# Sheet7.net
KiCad netlist of a schematic drawn in Altium Designer
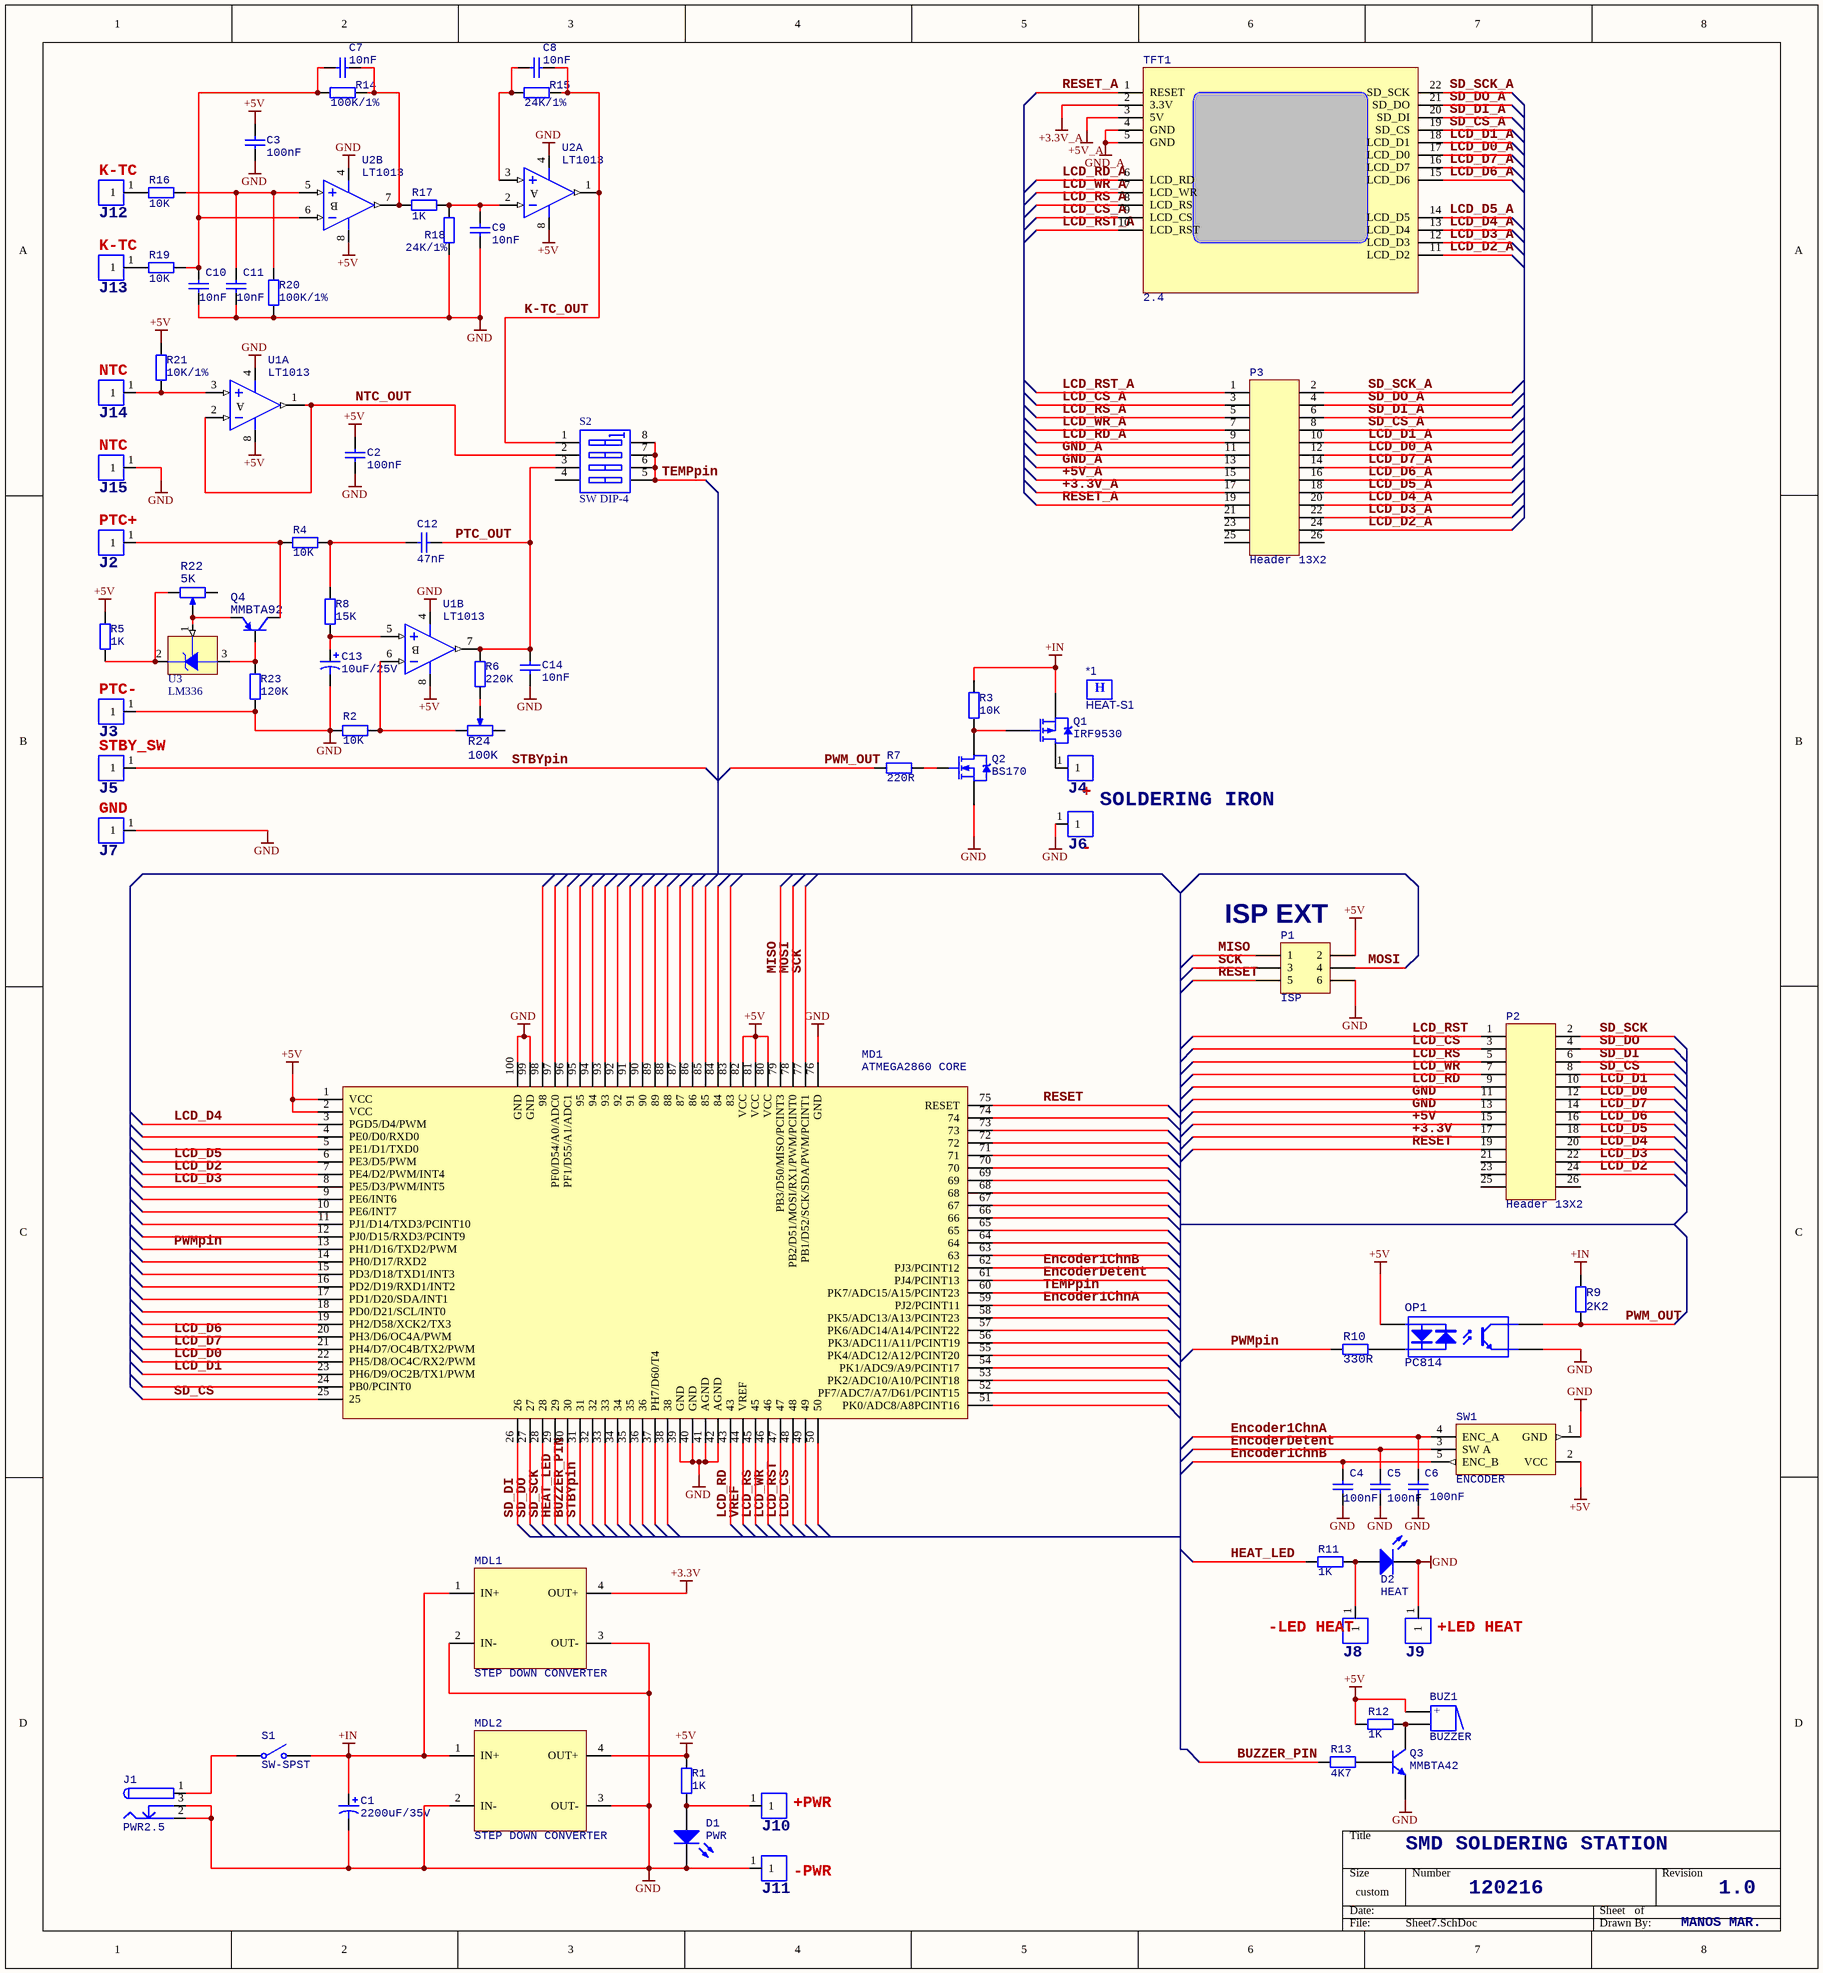
[diagram p0: Sheet7.SchDoc]

(export (version "E")
  (design (tool "Eeschema 10.0.6"))
  (components
    (comp (ref "*1")
      (value "HEAT-S1")
      (footprint "SK 104 HEATSHINK")
      (libsource (lib "SG_INTLIB") (part "HEAT-S1"))
    )
    (comp (ref "BUZ1") (value "BUZZER") (footprint "BUZZER") (libsource (lib "SMD STATION") (part "BUZZER")))
    (comp (ref "C1")
      (value "2200uF/35V")
      (footprint "RB5-10.5")
      (description "Polarized Capacitor (Radial)")
      (libsource (lib "Miscellaneous Devices") (part "Cap Pol1"))
    )
    (comp (ref "C2")
      (value "100nF")
      (footprint "0805")
      (description "Capacitor, Ceramic, 4.7uF 10% 16V 0805 (2012) X7R")
      (fields (field (name "TOLERANCE") "10 %"))
      (libsource (lib "AltiumDesignLibrary") (part "CAP-NP"))
    )
    (comp (ref "C3")
      (value "100nF")
      (footprint "0805")
      (description "Capacitor, Ceramic, 4.7uF 10% 16V 0805 (2012) X7R")
      (fields (field (name "TOLERANCE") "10 %"))
      (libsource (lib "AltiumDesignLibrary") (part "CAP-NP"))
    )
    (comp (ref "C4")
      (value "100nF")
      (footprint "0805")
      (description "Capacitor")
      (libsource (lib "Miscellaneous Devices") (part "Cap"))
    )
    (comp (ref "C5")
      (value "100nF")
      (footprint "0805")
      (description "Capacitor")
      (libsource (lib "Miscellaneous Devices") (part "Cap"))
    )
    (comp (ref "C6")
      (value "100nF")
      (footprint "0805")
      (description "Capacitor")
      (libsource (lib "Miscellaneous Devices") (part "Cap"))
    )
    (comp (ref "C7")
      (value "10nF")
      (footprint "0805")
      (description "Capacitor, Ceramic, 4.7uF 10% 16V 0805 (2012) X7R")
      (fields (field (name "TOLERANCE") "10 %"))
      (libsource (lib "AltiumDesignLibrary") (part "CAP-NP"))
    )
    (comp (ref "C8")
      (value "10nF")
      (footprint "0805")
      (description "Capacitor, Ceramic, 4.7uF 10% 16V 0805 (2012) X7R")
      (fields (field (name "TOLERANCE") "10 %"))
      (libsource (lib "AltiumDesignLibrary") (part "CAP-NP"))
    )
    (comp (ref "C9")
      (value "10nF")
      (footprint "0805")
      (description "Capacitor, Ceramic, 4.7uF 10% 16V 0805 (2012) X7R")
      (fields (field (name "TOLERANCE") "10 %"))
      (libsource (lib "AltiumDesignLibrary") (part "CAP-NP"))
    )
    (comp (ref "C10")
      (value "10nF")
      (footprint "0805")
      (description "Capacitor, Ceramic, 4.7uF 10% 16V 0805 (2012) X7R")
      (fields (field (name "TOLERANCE") "10 %"))
      (libsource (lib "AltiumDesignLibrary") (part "CAP-NP"))
    )
    (comp (ref "C11")
      (value "10nF")
      (footprint "0805")
      (description "Capacitor, Ceramic, 4.7uF 10% 16V 0805 (2012) X7R")
      (fields (field (name "TOLERANCE") "10 %"))
      (libsource (lib "AltiumDesignLibrary") (part "CAP-NP"))
    )
    (comp (ref "C12")
      (value "47nF")
      (footprint "0805")
      (description "Capacitor, Ceramic, 4.7uF 10% 16V 0805 (2012) X7R")
      (fields (field (name "TOLERANCE") "10 %"))
      (libsource (lib "AltiumDesignLibrary") (part "CAP-NP"))
    )
    (comp (ref "C13")
      (value "10uF/25V")
      (footprint "RB-08")
      (description "Polarized Capacitor (Radial)")
      (libsource (lib "Miscellaneous Devices") (part "Cap Pol1"))
    )
    (comp (ref "C14")
      (value "10nF")
      (footprint "0805")
      (description "Capacitor, Ceramic, 4.7uF 10% 16V 0805 (2012) X7R")
      (fields (field (name "TOLERANCE") "10 %"))
      (libsource (lib "AltiumDesignLibrary") (part "CAP-NP"))
    )
    (comp (ref "D1")
      (value "PWR")
      (footprint "1206D")
      (description "Typical INFRARED GaAs LED")
      (libsource (lib "Miscellaneous Devices") (part "LED0"))
    )
    (comp (ref "D2")
      (value "HEAT")
      (footprint "1206D")
      (description "Typical INFRARED GaAs LED")
      (libsource (lib "Miscellaneous Devices") (part "LED0"))
    )
    (comp (ref "J1")
      (value "PWR2.5")
      (footprint "POWER JACK")
      (description "Low Voltage Power Supply Connector")
      (libsource (lib "Miscellaneous Connectors") (part "PWR2.5"))
    )
    (comp (ref "J2")
      (value "PTC+")
      (footprint "CON2")
      (fields (field (name "MANUFACTURER") "Sta.Ge HELLAS"))
      (libsource (lib "") (part "CON1_S_1"))
    )
    (comp (ref "J3")
      (value "PTC-")
      (footprint "CON2")
      (fields (field (name "MANUFACTURER") "Sta.Ge HELLAS"))
      (libsource (lib "") (part "CON1_S_1"))
    )
    (comp (ref "J4")
      (value "+")
      (footprint "CON2")
      (fields (field (name "MANUFACTURER") "Sta.Ge HELLAS"))
      (libsource (lib "Z_General_SCH_Library") (part "CON1_S"))
    )
    (comp (ref "J5")
      (value "STBY_SW")
      (footprint "CON2")
      (fields (field (name "MANUFACTURER") "Sta.Ge HELLAS"))
      (libsource (lib "") (part "CON1_S_1"))
    )
    (comp (ref "J6")
      (value "-")
      (footprint "CON2")
      (fields (field (name "MANUFACTURER") "Sta.Ge HELLAS"))
      (libsource (lib "Z_General_SCH_Library") (part "CON1_S"))
    )
    (comp (ref "J7")
      (value "GND")
      (footprint "CON2")
      (fields (field (name "MANUFACTURER") "Sta.Ge HELLAS"))
      (libsource (lib "") (part "CON1_S_1"))
    )
    (comp (ref "J8")
      (value "-LED HEAT")
      (footprint "CON2")
      (fields (field (name "MANUFACTURER") "Sta.Ge HELLAS"))
      (libsource (lib "") (part "CON1_S_2"))
    )
    (comp (ref "J9")
      (value "+LED HEAT")
      (footprint "CON2")
      (fields (field (name "MANUFACTURER") "Sta.Ge HELLAS"))
      (libsource (lib "") (part "CON1_S_2"))
    )
    (comp (ref "J10")
      (value "+PWR")
      (footprint "CON2")
      (fields (field (name "MANUFACTURER") "Sta.Ge HELLAS"))
      (libsource (lib "Z_General_SCH_Library") (part "CON1_S"))
    )
    (comp (ref "J11")
      (value "-PWR")
      (footprint "CON2")
      (fields (field (name "MANUFACTURER") "Sta.Ge HELLAS"))
      (libsource (lib "Z_General_SCH_Library") (part "CON1_S"))
    )
    (comp (ref "J12")
      (value "K-TC")
      (footprint "CON2")
      (fields (field (name "MANUFACTURER") "Sta.Ge HELLAS"))
      (libsource (lib "") (part "CON1_S_1"))
    )
    (comp (ref "J13")
      (value "K-TC")
      (footprint "CON2")
      (fields (field (name "MANUFACTURER") "Sta.Ge HELLAS"))
      (libsource (lib "") (part "CON1_S_1"))
    )
    (comp (ref "J14")
      (value "NTC")
      (footprint "CON2")
      (fields (field (name "MANUFACTURER") "Sta.Ge HELLAS"))
      (libsource (lib "") (part "CON1_S_1"))
    )
    (comp (ref "J15")
      (value "NTC")
      (footprint "CON2")
      (fields (field (name "MANUFACTURER") "Sta.Ge HELLAS"))
      (libsource (lib "") (part "CON1_S_1"))
    )
    (comp (ref "MD1")
      (value "ATMEGA2860 CORE")
      (footprint "ATMEGA 2560 CORE")
      (libsource (lib "SMD STATION") (part "ATMEGA2560 CORE"))
    )
    (comp (ref "MDL1")
      (value "STEP DOWN CONVERTER")
      (footprint "STEP DOWN CONVERTER MINI")
      (libsource (lib "SMD STATION") (part "STEP DOWN CONVERTER"))
    )
    (comp (ref "MDL2")
      (value "STEP DOWN CONVERTER")
      (footprint "STEP DOWN CONVERTER MINI")
      (libsource (lib "SMD STATION") (part "STEP DOWN CONVERTER"))
    )
    (comp (ref "OP1")
      (value "PC814")
      (footprint "SOP-4")
      (description "AC OPTOCUPLER")
      (libsource (lib "STAGE_MP3") (part "OPTO-AC1"))
    )
    (comp (ref "P1")
      (value "ISP")
      (footprint "HDR2X3")
      (description "Header, 3-Pin, Dual row")
      (libsource (lib "Miscellaneous Connectors") (part "Header 3X2"))
    )
    (comp (ref "P2")
      (value "Header 13X2")
      (footprint "IDC2.54-V26A")
      (description "Header, 13-Pin, Dual row")
      (libsource (lib "Miscellaneous Connectors") (part "Header 13X2"))
    )
    (comp (ref "P3")
      (value "Header 13X2")
      (footprint "IDC2.54-V26A")
      (description "Header, 13-Pin, Dual row")
      (libsource (lib "Miscellaneous Connectors") (part "Header 13X2"))
    )
    (comp (ref "Q1")
      (value "IRF9530")
      (footprint "TO-220V")
      (description "P-Channel Power MOSFET")
      (libsource (lib "Miscellaneous Devices") (part "PMOS-2"))
    )
    (comp (ref "Q2")
      (value "BS170")
      (footprint "T0-92")
      (description "N-Channel Power MOSFET")
      (libsource (lib "Miscellaneous Devices") (part "NMOS-2"))
    )
    (comp (ref "Q3")
      (value "MMBTA42")
      (footprint "SO-G3")
      (description "NPN Bipolar Transistor")
      (libsource (lib "Miscellaneous Devices") (part "NPN"))
    )
    (comp (ref "Q4")
      (value "MMBTA92")
      (footprint "SO-G3")
      (description "PNP Bipolar Transistor")
      (libsource (lib "Miscellaneous Devices") (part "PNP"))
    )
    (comp (ref "R1")
      (value "1K")
      (footprint "0805")
      (description "Resistor")
      (libsource (lib "Miscellaneous Devices") (part "Res2"))
    )
    (comp (ref "R2")
      (value "10K")
      (footprint "0805")
      (fields
        (field (name "MANUFACTURER") "Generic Components")
        (field (name "POWER") "0,2W")
        (field (name "SGPARTNUMBER") "R001051")
      )
      (libsource (lib "") (part "RES_1"))
    )
    (comp (ref "R3")
      (value "10K")
      (footprint "0805")
      (description "Resistor")
      (libsource (lib "Miscellaneous Devices") (part "Res2"))
    )
    (comp (ref "R4")
      (value "10K")
      (footprint "0805")
      (fields
        (field (name "MANUFACTURER") "Generic Components")
        (field (name "POWER") "0,2W")
        (field (name "SGPARTNUMBER") "R001051")
      )
      (libsource (lib "") (part "RES_2"))
    )
    (comp (ref "R5")
      (value "1K")
      (footprint "0805")
      (fields
        (field (name "MANUFACTURER") "Generic Components")
        (field (name "POWER") "0,2W")
        (field (name "SGPARTNUMBER") "R001051")
      )
      (libsource (lib "SG_PCB") (part "RES"))
    )
    (comp (ref "R6")
      (value "220K")
      (footprint "0805")
      (fields
        (field (name "MANUFACTURER") "Generic Components")
        (field (name "POWER") "0,2W")
        (field (name "SGPARTNUMBER") "R001051")
      )
      (libsource (lib "") (part "RES_3"))
    )
    (comp (ref "R7")
      (value "220R")
      (footprint "0805")
      (description "Resistor")
      (libsource (lib "") (part "Res2_1"))
    )
    (comp (ref "R8")
      (value "15K")
      (footprint "0805")
      (fields
        (field (name "MANUFACTURER") "Generic Components")
        (field (name "POWER") "0,2W")
        (field (name "SGPARTNUMBER") "R001051")
      )
      (libsource (lib "") (part "RES_3"))
    )
    (comp (ref "R9")
      (value "2K2")
      (footprint "0805")
      (fields
        (field (name "MANUFACTURER") "Generic Components")
        (field (name "POWER") "0,2W")
        (field (name "SGPARTNUMBER") "R001051")
      )
      (libsource (lib "") (part "RES_3"))
    )
    (comp (ref "R10")
      (value "330R")
      (footprint "0805")
      (fields
        (field (name "MANUFACTURER") "Generic Components")
        (field (name "POWER") "0,2W")
        (field (name "SGPARTNUMBER") "R001051")
      )
      (libsource (lib "") (part "RES_1"))
    )
    (comp (ref "R11")
      (value "1K")
      (footprint "0805")
      (description "Resistor")
      (libsource (lib "") (part "Res2_1"))
    )
    (comp (ref "R12")
      (value "1K")
      (footprint "0805")
      (fields
        (field (name "MANUFACTURER") "Generic Components")
        (field (name "POWER") "0,2W")
        (field (name "SGPARTNUMBER") "R001051")
      )
      (libsource (lib "") (part "RES_1"))
    )
    (comp (ref "R13")
      (value "4K7")
      (footprint "0805")
      (fields
        (field (name "MANUFACTURER") "Generic Components")
        (field (name "POWER") "0,2W")
        (field (name "SGPARTNUMBER") "R001051")
      )
      (libsource (lib "") (part "RES_2"))
    )
    (comp (ref "R14")
      (value "100K/1%")
      (footprint "0805")
      (fields
        (field (name "MANUFACTURER") "Generic Components")
        (field (name "POWER") "0,2W")
        (field (name "SGPARTNUMBER") "R001051")
      )
      (libsource (lib "") (part "RES_1"))
    )
    (comp (ref "R15")
      (value "24K/1%")
      (footprint "0805")
      (fields
        (field (name "MANUFACTURER") "Generic Components")
        (field (name "POWER") "0,2W")
        (field (name "SGPARTNUMBER") "R001051")
      )
      (libsource (lib "") (part "RES_1"))
    )
    (comp (ref "R16")
      (value "10K")
      (footprint "0805")
      (fields
        (field (name "MANUFACTURER") "Generic Components")
        (field (name "POWER") "0,2W")
        (field (name "SGPARTNUMBER") "R001051")
      )
      (libsource (lib "") (part "RES_1"))
    )
    (comp (ref "R17")
      (value "1K")
      (footprint "0805")
      (fields
        (field (name "MANUFACTURER") "Generic Components")
        (field (name "POWER") "0,2W")
        (field (name "SGPARTNUMBER") "R001051")
      )
      (libsource (lib "") (part "RES_1"))
    )
    (comp (ref "R18")
      (value "24K/1%")
      (footprint "0805")
      (fields
        (field (name "MANUFACTURER") "Generic Components")
        (field (name "POWER") "0,2W")
        (field (name "SGPARTNUMBER") "R001051")
      )
      (libsource (lib "") (part "RES_3"))
    )
    (comp (ref "R19")
      (value "10K")
      (footprint "0805")
      (fields
        (field (name "MANUFACTURER") "Generic Components")
        (field (name "POWER") "0,2W")
        (field (name "SGPARTNUMBER") "R001051")
      )
      (libsource (lib "") (part "RES_1"))
    )
    (comp (ref "R20")
      (value "100K/1%")
      (footprint "0805")
      (fields
        (field (name "MANUFACTURER") "Generic Components")
        (field (name "POWER") "0,2W")
        (field (name "SGPARTNUMBER") "R001051")
      )
      (libsource (lib "SG_PCB") (part "RES"))
    )
    (comp (ref "R21")
      (value "10K/1%")
      (footprint "0805")
      (fields
        (field (name "MANUFACTURER") "Generic Components")
        (field (name "POWER") "0,2W")
        (field (name "SGPARTNUMBER") "R001051")
      )
      (libsource (lib "AVR SMD SOLDERING") (part "RES"))
    )
    (comp (ref "R22")
      (value "5K")
      (footprint "VR6")
      (fields
        (field (name "MANUFACTURER") "Sta.Ge HELLAS")
        (field (name "SGPARTNUMBER") "R001049")
        (field (name "PART NUMBER") "R002107")
      )
      (libsource (lib "") (part "RPot2_1"))
    )
    (comp (ref "R23")
      (value "120K")
      (footprint "0805")
      (fields
        (field (name "MANUFACTURER") "Generic Components")
        (field (name "POWER") "0,2W")
        (field (name "SGPARTNUMBER") "R001051")
      )
      (libsource (lib "SG_PCB") (part "RES"))
    )
    (comp (ref "R24")
      (value "100K")
      (footprint "VR6")
      (fields
        (field (name "MANUFACTURER") "Sta.Ge HELLAS")
        (field (name "SGPARTNUMBER") "R001049")
        (field (name "PART NUMBER") "R002107")
      )
      (libsource (lib "SG_INTLIB") (part "RPot2"))
    )
    (comp (ref "S1")
      (value "SW-SPST")
      (footprint "SPST-2")
      (description "Single-Pole, Single-Throw Switch")
      (libsource (lib "Miscellaneous Devices") (part "SW-SPST"))
    )
    (comp (ref "S2")
      (value "SW DIP-4")
      (footprint "DIP-8")
      (description "DIP Switch, 4 Position, SPST")
      (libsource (lib "Miscellaneous Devices") (part "SW DIP-4"))
    )
    (comp (ref "SW1")
      (value "ENCODER")
      (footprint "HDR1X5")
      (libsource (lib "SMD STATION") (part "ROTARY ENC"))
    )
    (comp (ref "TFT1")
      (value "2.4")
      (footprint "ARDUINO UNO")
      (libsource (lib "SMD STATION") (part "2.4 TFT SHIELD MCUFRIEND"))
    )
    (comp (ref "U1")
      (value "LT1013")
      (footprint "DIP-8")
      (description "Dual Precision Operational Amplifier")
      (libsource (lib "LT Operational Amplifier") (part "LT1013ACJ8"))
    )
    (comp (ref "U2")
      (value "LT1013")
      (footprint "DIP-8")
      (description "Dual Precision Operational Amplifier")
      (libsource (lib "LT Operational Amplifier") (part "LT1013ACJ8"))
    )
    (comp (ref "U3")
      (value "LM336")
      (footprint "Z03A")
      (description "Adjustable Micropower Voltage Reference")
      (libsource (lib "NSC Power Mgt Voltage Reference") (part "LM385Z"))
    )
  )
  (nets
    (net (code "1") (name "+3.3V") (class "Default")
      (node (ref "MDL1") (pin "4") (pinfunction "OUT+_4") (pintype "passive"))
      (node (ref "P2") (pin "17") (pinfunction "17_17") (pintype "passive"))
    )
    (net (code "2") (name "+3.3V_A") (class "Default")
      (node (ref "P3") (pin "17") (pinfunction "17_17") (pintype "passive"))
      (node (ref "TFT1") (pin "2") (pinfunction "3.3V_2") (pintype "passive"))
    )
    (net (code "3") (name "+5V") (class "Default")
      (node (ref "BUZ1") (pin "1") (pinfunction "1_1") (pintype "passive"))
      (node (ref "C2") (pin "2") (pinfunction "2_2") (pintype "passive"))
      (node (ref "C3") (pin "2") (pinfunction "2_2") (pintype "passive"))
      (node (ref "MD1") (pin "1") (pinfunction "VCC_1") (pintype "passive"))
      (node (ref "MD1") (pin "2") (pinfunction "VCC_2") (pintype "passive"))
      (node (ref "MD1") (pin "80") (pinfunction "VCC_80") (pintype "passive"))
      (node (ref "MD1") (pin "81") (pinfunction "VCC_81") (pintype "passive"))
      (node (ref "MD1") (pin "82") (pinfunction "VCC_82") (pintype "passive"))
      (node (ref "MDL2") (pin "4") (pinfunction "OUT+_4") (pintype "passive"))
      (node (ref "OP1") (pin "1") (pinfunction "A_1") (pintype "passive"))
      (node (ref "P1") (pin "2") (pinfunction "2_2") (pintype "passive"))
      (node (ref "P2") (pin "15") (pinfunction "15_15") (pintype "passive"))
      (node (ref "R1") (pin "2") (pinfunction "2_2") (pintype "passive"))
      (node (ref "R12") (pin "2") (pinfunction "2_2") (pintype "passive"))
      (node (ref "R21") (pin "2") (pinfunction "2_2") (pintype "passive"))
      (node (ref "R5") (pin "2") (pinfunction "2_2") (pintype "passive"))
      (node (ref "SW1") (pin "2") (pinfunction "VCC_2") (pintype "passive"))
      (node (ref "U1") (pin "8") (pinfunction "V+_8") (pintype "power_in"))
      (node (ref "U2") (pin "8") (pinfunction "V+_8") (pintype "power_in"))
    )
    (net (code "4") (name "+5V_A") (class "Default")
      (node (ref "P3") (pin "15") (pinfunction "15_15") (pintype "passive"))
      (node (ref "TFT1") (pin "3") (pinfunction "5V_3") (pintype "passive"))
    )
    (net (code "5") (name "+IN") (class "Default")
      (node (ref "C1") (pin "1") (pinfunction "1_1") (pintype "passive"))
      (node (ref "MDL1") (pin "1") (pinfunction "IN+_1") (pintype "passive"))
      (node (ref "MDL2") (pin "1") (pinfunction "IN+_1") (pintype "passive"))
      (node (ref "Q1") (pin "3") (pinfunction "S_3") (pintype "passive"))
      (node (ref "R3") (pin "2") (pinfunction "2_2") (pintype "passive"))
      (node (ref "R9") (pin "1") (pinfunction "1_1") (pintype "passive"))
      (node (ref "S1") (pin "2") (pinfunction "NO_2") (pintype "passive"))
    )
    (net (code "6") (name "/BUZZER_PIN") (class "Default")
      (node (ref "MD1") (pin "30") (pinfunction "30_30") (pintype "passive"))
      (node (ref "R13") (pin "1") (pinfunction "1_1") (pintype "passive"))
    )
    (net (code "7") (name "/Encoder1ChnA") (class "Default")
      (node (ref "C6") (pin "1") (pinfunction "1_1") (pintype "passive"))
      (node (ref "MD1") (pin "59") (pinfunction "PJ2/PCINT11_59") (pintype "passive"))
      (node (ref "SW1") (pin "4") (pinfunction "ENC_A_4") (pintype "passive"))
    )
    (net (code "8") (name "/Encoder1ChnB") (class "Default")
      (node (ref "C4") (pin "1") (pinfunction "1_1") (pintype "passive"))
      (node (ref "MD1") (pin "62") (pinfunction "PJ3/PCINT12_62") (pintype "passive"))
      (node (ref "SW1") (pin "5") (pinfunction "ENC_B_5") (pintype "output"))
    )
    (net (code "9") (name "/EncoderDetent") (class "Default")
      (node (ref "C5") (pin "1") (pinfunction "1_1") (pintype "passive"))
      (node (ref "MD1") (pin "61") (pinfunction "PJ4/PCINT13_61") (pintype "passive"))
      (node (ref "SW1") (pin "3") (pinfunction "SW_A_3") (pintype "passive"))
    )
    (net (code "10") (name "/HEAT_LED") (class "Default")
      (node (ref "MD1") (pin "29") (pinfunction "29_29") (pintype "passive"))
      (node (ref "R11") (pin "1") (pinfunction "1_1") (pintype "passive"))
    )
    (net (code "11") (name "/K-TC_OUT") (class "Default")
      (node (ref "C8") (pin "1") (pinfunction "1_1") (pintype "passive"))
      (node (ref "R15") (pin "1") (pinfunction "1_1") (pintype "passive"))
      (node (ref "S2") (pin "1") (pinfunction "A1_1") (pintype "passive"))
      (node (ref "U2") (pin "1") (pinfunction "OUT_1") (pintype "output"))
    )
    (net (code "12") (name "/LCD_CS") (class "Default")
      (node (ref "MD1") (pin "48") (pinfunction "48_48") (pintype "passive"))
      (node (ref "P2") (pin "3") (pinfunction "3_3") (pintype "passive"))
    )
    (net (code "13") (name "/LCD_CS_A") (class "Default")
      (node (ref "P3") (pin "3") (pinfunction "3_3") (pintype "passive"))
      (node (ref "TFT1") (pin "9") (pinfunction "LCD_CS_9") (pintype "passive"))
    )
    (net (code "14") (name "/LCD_D0") (class "Default")
      (node (ref "MD1") (pin "22") (pinfunction "PH5/D8/OC4C/RX2/PWM_22") (pintype "passive"))
      (node (ref "P2") (pin "12") (pinfunction "12_12") (pintype "passive"))
    )
    (net (code "15") (name "/LCD_D0_A") (class "Default")
      (node (ref "P3") (pin "12") (pinfunction "12_12") (pintype "passive"))
      (node (ref "TFT1") (pin "17") (pinfunction "LCD_D0_17") (pintype "passive"))
    )
    (net (code "16") (name "/LCD_D1") (class "Default")
      (node (ref "MD1") (pin "23") (pinfunction "PH6/D9/OC2B/TX1/PWM_23") (pintype "passive"))
      (node (ref "P2") (pin "10") (pinfunction "10_10") (pintype "passive"))
    )
    (net (code "17") (name "/LCD_D1_A") (class "Default")
      (node (ref "P3") (pin "10") (pinfunction "10_10") (pintype "passive"))
      (node (ref "TFT1") (pin "18") (pinfunction "LCD_D1_18") (pintype "passive"))
    )
    (net (code "18") (name "/LCD_D2") (class "Default")
      (node (ref "MD1") (pin "7") (pinfunction "PE4/D2/PWM/INT4_7") (pintype "passive"))
      (node (ref "P2") (pin "24") (pinfunction "24_24") (pintype "passive"))
    )
    (net (code "19") (name "/LCD_D2_A") (class "Default")
      (node (ref "P3") (pin "24") (pinfunction "24_24") (pintype "passive"))
      (node (ref "TFT1") (pin "11") (pinfunction "LCD_D2_11") (pintype "passive"))
    )
    (net (code "20") (name "/LCD_D3") (class "Default")
      (node (ref "MD1") (pin "8") (pinfunction "PE5/D3/PWM/INT5_8") (pintype "passive"))
      (node (ref "P2") (pin "22") (pinfunction "22_22") (pintype "passive"))
    )
    (net (code "21") (name "/LCD_D3_A") (class "Default")
      (node (ref "P3") (pin "22") (pinfunction "22_22") (pintype "passive"))
      (node (ref "TFT1") (pin "12") (pinfunction "LCD_D3_12") (pintype "passive"))
    )
    (net (code "22") (name "/LCD_D4") (class "Default")
      (node (ref "MD1") (pin "3") (pinfunction "PGD5/D4/PWM_3") (pintype "passive"))
      (node (ref "P2") (pin "20") (pinfunction "20_20") (pintype "passive"))
    )
    (net (code "23") (name "/LCD_D4_A") (class "Default")
      (node (ref "P3") (pin "20") (pinfunction "20_20") (pintype "passive"))
      (node (ref "TFT1") (pin "13") (pinfunction "LCD_D4_13") (pintype "passive"))
    )
    (net (code "24") (name "/LCD_D5") (class "Default")
      (node (ref "MD1") (pin "6") (pinfunction "PE3/D5/PWM_6") (pintype "passive"))
      (node (ref "P2") (pin "18") (pinfunction "18_18") (pintype "passive"))
    )
    (net (code "25") (name "/LCD_D5_A") (class "Default")
      (node (ref "P3") (pin "18") (pinfunction "18_18") (pintype "passive"))
      (node (ref "TFT1") (pin "14") (pinfunction "LCD_D5_14") (pintype "passive"))
    )
    (net (code "26") (name "/LCD_D6") (class "Default")
      (node (ref "MD1") (pin "20") (pinfunction "PH3/D6/OC4A/PWM_20") (pintype "passive"))
      (node (ref "P2") (pin "16") (pinfunction "16_16") (pintype "passive"))
    )
    (net (code "27") (name "/LCD_D6_A") (class "Default")
      (node (ref "P3") (pin "16") (pinfunction "16_16") (pintype "passive"))
      (node (ref "TFT1") (pin "15") (pinfunction "LCD_D6_15") (pintype "passive"))
    )
    (net (code "28") (name "/LCD_D7") (class "Default")
      (node (ref "MD1") (pin "21") (pinfunction "PH4/D7/OC4B/TX2/PWM_21") (pintype "passive"))
      (node (ref "P2") (pin "14") (pinfunction "14_14") (pintype "passive"))
    )
    (net (code "29") (name "/LCD_D7_A") (class "Default")
      (node (ref "P3") (pin "14") (pinfunction "14_14") (pintype "passive"))
      (node (ref "TFT1") (pin "16") (pinfunction "LCD_D7_16") (pintype "passive"))
    )
    (net (code "30") (name "/LCD_RD") (class "Default")
      (node (ref "MD1") (pin "43") (pinfunction "43_43") (pintype "passive"))
      (node (ref "P2") (pin "9") (pinfunction "9_9") (pintype "passive"))
    )
    (net (code "31") (name "/LCD_RD_A") (class "Default")
      (node (ref "P3") (pin "9") (pinfunction "9_9") (pintype "passive"))
      (node (ref "TFT1") (pin "6") (pinfunction "LCD_RD_6") (pintype "passive"))
    )
    (net (code "32") (name "/LCD_RS") (class "Default")
      (node (ref "MD1") (pin "45") (pinfunction "45_45") (pintype "passive"))
      (node (ref "P2") (pin "5") (pinfunction "5_5") (pintype "passive"))
    )
    (net (code "33") (name "/LCD_RST") (class "Default")
      (node (ref "MD1") (pin "47") (pinfunction "47_47") (pintype "passive"))
      (node (ref "P2") (pin "1") (pinfunction "1_1") (pintype "passive"))
    )
    (net (code "34") (name "/LCD_RST_A") (class "Default")
      (node (ref "P3") (pin "1") (pinfunction "1_1") (pintype "passive"))
      (node (ref "TFT1") (pin "10") (pinfunction "LCD_RST_10") (pintype "passive"))
    )
    (net (code "35") (name "/LCD_RS_A") (class "Default")
      (node (ref "P3") (pin "5") (pinfunction "5_5") (pintype "passive"))
      (node (ref "TFT1") (pin "8") (pinfunction "LCD_RS_8") (pintype "passive"))
    )
    (net (code "36") (name "/LCD_WR") (class "Default")
      (node (ref "MD1") (pin "46") (pinfunction "46_46") (pintype "passive"))
      (node (ref "P2") (pin "7") (pinfunction "7_7") (pintype "passive"))
    )
    (net (code "37") (name "/LCD_WR_A") (class "Default")
      (node (ref "P3") (pin "7") (pinfunction "7_7") (pintype "passive"))
      (node (ref "TFT1") (pin "7") (pinfunction "LCD_WR_7") (pintype "passive"))
    )
    (net (code "38") (name "/MISO") (class "Default")
      (node (ref "MD1") (pin "79") (pinfunction "PB3/D50/MISO/PCINT3_79") (pintype "passive"))
      (node (ref "P1") (pin "1") (pinfunction "1_1") (pintype "passive"))
    )
    (net (code "39") (name "/MOSI") (class "Default")
      (node (ref "MD1") (pin "78") (pinfunction "PB2/D51/MOSI/RX1/PWM/PCINT0_78") (pintype "passive"))
      (node (ref "P1") (pin "4") (pinfunction "4_4") (pintype "passive"))
    )
    (net (code "40") (name "/NTC_OUT") (class "Default")
      (node (ref "S2") (pin "2") (pinfunction "A2_2") (pintype "passive"))
      (node (ref "U1") (pin "1") (pinfunction "OUT_1") (pintype "output"))
      (node (ref "U1") (pin "2") (pinfunction "IN-_2") (pintype "input"))
    )
    (net (code "41") (name "/PTC_OUT") (class "Default")
      (node (ref "C12") (pin "1") (pinfunction "1_1") (pintype "passive"))
      (node (ref "C14") (pin "2") (pinfunction "2_2") (pintype "passive"))
      (node (ref "R6") (pin "1") (pinfunction "1_1") (pintype "passive"))
      (node (ref "S2") (pin "3") (pinfunction "A3_3") (pintype "passive"))
      (node (ref "U1") (pin "7") (pinfunction "OUT_7") (pintype "output"))
    )
    (net (code "42") (name "/PWM_OUT") (class "Default")
      (node (ref "OP1") (pin "4") (pinfunction "C_4") (pintype "passive"))
      (node (ref "R7") (pin "1") (pinfunction "1_1") (pintype "passive"))
      (node (ref "R9") (pin "2") (pinfunction "2_2") (pintype "passive"))
    )
    (net (code "43") (name "/PWMpin") (class "Default")
      (node (ref "MD1") (pin "13") (pinfunction "PH1/D16/TXD2/PWM_13") (pintype "passive"))
      (node (ref "R10") (pin "2") (pinfunction "2_2") (pintype "passive"))
    )
    (net (code "44") (name "/RESET") (class "Default")
      (node (ref "MD1") (pin "75") (pinfunction "RESET_75") (pintype "passive"))
      (node (ref "P1") (pin "5") (pinfunction "5_5") (pintype "passive"))
      (node (ref "P2") (pin "19") (pinfunction "19_19") (pintype "passive"))
    )
    (net (code "45") (name "/RESET_A") (class "Default")
      (node (ref "P3") (pin "19") (pinfunction "19_19") (pintype "passive"))
      (node (ref "TFT1") (pin "1") (pinfunction "RESET_1") (pintype "passive"))
    )
    (net (code "46") (name "/SCK") (class "Default")
      (node (ref "MD1") (pin "77") (pinfunction "PB1/D52/SCK/SDA/PWM/PCINT1_77") (pintype "passive"))
      (node (ref "P1") (pin "3") (pinfunction "3_3") (pintype "passive"))
    )
    (net (code "47") (name "/SD_CS") (class "Default")
      (node (ref "MD1") (pin "25") (pinfunction "25_25") (pintype "passive"))
      (node (ref "P2") (pin "8") (pinfunction "8_8") (pintype "passive"))
    )
    (net (code "48") (name "/SD_CS_A") (class "Default")
      (node (ref "P3") (pin "8") (pinfunction "8_8") (pintype "passive"))
      (node (ref "TFT1") (pin "19") (pinfunction "SD_CS_19") (pintype "passive"))
    )
    (net (code "49") (name "/SD_DI") (class "Default")
      (node (ref "MD1") (pin "26") (pinfunction "26_26") (pintype "passive"))
      (node (ref "P2") (pin "6") (pinfunction "6_6") (pintype "passive"))
    )
    (net (code "50") (name "/SD_DI_A") (class "Default")
      (node (ref "P3") (pin "6") (pinfunction "6_6") (pintype "passive"))
      (node (ref "TFT1") (pin "20") (pinfunction "SD_DI_20") (pintype "passive"))
    )
    (net (code "51") (name "/SD_DO") (class "Default")
      (node (ref "MD1") (pin "27") (pinfunction "27_27") (pintype "passive"))
      (node (ref "P2") (pin "4") (pinfunction "4_4") (pintype "passive"))
    )
    (net (code "52") (name "/SD_DO_A") (class "Default")
      (node (ref "P3") (pin "4") (pinfunction "4_4") (pintype "passive"))
      (node (ref "TFT1") (pin "21") (pinfunction "SD_DO_21") (pintype "passive"))
    )
    (net (code "53") (name "/SD_SCK") (class "Default")
      (node (ref "MD1") (pin "28") (pinfunction "28_28") (pintype "passive"))
      (node (ref "P2") (pin "2") (pinfunction "2_2") (pintype "passive"))
    )
    (net (code "54") (name "/SD_SCK_A") (class "Default")
      (node (ref "P3") (pin "2") (pinfunction "2_2") (pintype "passive"))
      (node (ref "TFT1") (pin "22") (pinfunction "SD_SCK_22") (pintype "passive"))
    )
    (net (code "55") (name "/STBYpin") (class "Default")
      (node (ref "J5") (pin "1") (pinfunction "1_1") (pintype "passive"))
      (node (ref "MD1") (pin "31") (pinfunction "31_31") (pintype "passive"))
    )
    (net (code "56") (name "/TEMPpin") (class "Default")
      (node (ref "MD1") (pin "60") (pinfunction "PK7/ADC15/A15/PCINT23_60") (pintype "passive"))
      (node (ref "S2") (pin "5") (pinfunction "B4_5") (pintype "passive"))
      (node (ref "S2") (pin "6") (pinfunction "B3_6") (pintype "passive"))
      (node (ref "S2") (pin "7") (pinfunction "B2_7") (pintype "passive"))
      (node (ref "S2") (pin "8") (pinfunction "B1_8") (pintype "passive"))
    )
    (net (code "57") (name "/VREF") (class "Default")
      (node (ref "MD1") (pin "44") (pinfunction "VREF_44") (pintype "passive"))
    )
    (net (code "58") (name "GND") (class "Default")
      (node (ref "C1") (pin "2") (pinfunction "2_2") (pintype "passive"))
      (node (ref "C10") (pin "1") (pinfunction "1_1") (pintype "passive"))
      (node (ref "C11") (pin "1") (pinfunction "1_1") (pintype "passive"))
      (node (ref "C13") (pin "2") (pinfunction "2_2") (pintype "passive"))
      (node (ref "C14") (pin "1") (pinfunction "1_1") (pintype "passive"))
      (node (ref "C2") (pin "1") (pinfunction "1_1") (pintype "passive"))
      (node (ref "C3") (pin "1") (pinfunction "1_1") (pintype "passive"))
      (node (ref "C4") (pin "2") (pinfunction "2_2") (pintype "passive"))
      (node (ref "C5") (pin "2") (pinfunction "2_2") (pintype "passive"))
      (node (ref "C6") (pin "2") (pinfunction "2_2") (pintype "passive"))
      (node (ref "C9") (pin "2") (pinfunction "2_2") (pintype "passive"))
      (node (ref "D1") (pin "2") (pinfunction "K_2") (pintype "passive"))
      (node (ref "D2") (pin "2") (pinfunction "K_2") (pintype "passive"))
      (node (ref "J1") (pin "2") (pinfunction "2_2") (pintype "power_in"))
      (node (ref "J1") (pin "3") (pinfunction "3_3") (pintype "power_in"))
      (node (ref "J11") (pin "1") (pinfunction "1_1") (pintype "passive"))
      (node (ref "J15") (pin "1") (pinfunction "1_1") (pintype "passive"))
      (node (ref "J3") (pin "1") (pinfunction "1_1") (pintype "passive"))
      (node (ref "J6") (pin "1") (pinfunction "1_1") (pintype "passive"))
      (node (ref "J7") (pin "1") (pinfunction "1_1") (pintype "passive"))
      (node (ref "J9") (pin "1") (pinfunction "1_1") (pintype "passive"))
      (node (ref "MD1") (pin "100") (pinfunction "GND_100") (pintype "passive"))
      (node (ref "MD1") (pin "39") (pinfunction "GND_39") (pintype "passive"))
      (node (ref "MD1") (pin "40") (pinfunction "GND_40") (pintype "passive"))
      (node (ref "MD1") (pin "41") (pinfunction "AGND_41") (pintype "passive"))
      (node (ref "MD1") (pin "42") (pinfunction "AGND_42") (pintype "passive"))
      (node (ref "MD1") (pin "76") (pinfunction "GND_76") (pintype "passive"))
      (node (ref "MD1") (pin "99") (pinfunction "GND_99") (pintype "passive"))
      (node (ref "MDL1") (pin "2") (pinfunction "IN-_2") (pintype "passive"))
      (node (ref "MDL1") (pin "3") (pinfunction "OUT-_3") (pintype "passive"))
      (node (ref "MDL2") (pin "2") (pinfunction "IN-_2") (pintype "passive"))
      (node (ref "MDL2") (pin "3") (pinfunction "OUT-_3") (pintype "passive"))
      (node (ref "OP1") (pin "3") (pinfunction "E_3") (pintype "passive"))
      (node (ref "P1") (pin "6") (pinfunction "6_6") (pintype "passive"))
      (node (ref "P2") (pin "11") (pinfunction "11_11") (pintype "passive"))
      (node (ref "P2") (pin "13") (pinfunction "13_13") (pintype "passive"))
      (node (ref "Q2") (pin "3") (pinfunction "S_3") (pintype "passive"))
      (node (ref "Q3") (pin "2") (pinfunction "E_2") (pintype "passive"))
      (node (ref "R18") (pin "2") (pinfunction "2_2") (pintype "passive"))
      (node (ref "R2") (pin "2") (pinfunction "2_2") (pintype "passive"))
      (node (ref "R20") (pin "1") (pinfunction "1_1") (pintype "passive"))
      (node (ref "R23") (pin "1") (pinfunction "1_1") (pintype "passive"))
      (node (ref "SW1") (pin "1") (pinfunction "GND_1") (pintype "output"))
      (node (ref "U1") (pin "4") (pinfunction "V-_4") (pintype "power_in"))
      (node (ref "U2") (pin "4") (pinfunction "V-_4") (pintype "power_in"))
    )
    (net (code "59") (name "GND_A") (class "Default")
      (node (ref "P3") (pin "11") (pinfunction "11_11") (pintype "passive"))
      (node (ref "P3") (pin "13") (pinfunction "13_13") (pintype "passive"))
      (node (ref "TFT1") (pin "4") (pinfunction "GND_4") (pintype "passive"))
      (node (ref "TFT1") (pin "5") (pinfunction "GND_5") (pintype "passive"))
    )
    (net (code "60") (name "Net-(C12-Pad2)") (class "Default")
      (node (ref "C12") (pin "2") (pinfunction "2_2") (pintype "passive"))
      (node (ref "R4") (pin "2") (pinfunction "2_2") (pintype "passive"))
      (node (ref "R8") (pin "1") (pinfunction "1_1") (pintype "passive"))
    )
    (net (code "61") (name "Net-(D1-A)") (class "Default")
      (node (ref "D1") (pin "1") (pinfunction "A_1") (pintype "passive"))
      (node (ref "J10") (pin "1") (pinfunction "1_1") (pintype "passive"))
      (node (ref "R1") (pin "1") (pinfunction "1_1") (pintype "passive"))
    )
    (net (code "62") (name "Net-(D2-A)") (class "Default")
      (node (ref "D2") (pin "1") (pinfunction "A_1") (pintype "passive"))
      (node (ref "J8") (pin "1") (pinfunction "1_1") (pintype "passive"))
      (node (ref "R11") (pin "2") (pinfunction "2_2") (pintype "passive"))
    )
    (net (code "63") (name "Net-(J12-Pad1)") (class "Default")
      (node (ref "J12") (pin "1") (pinfunction "1_1") (pintype "passive"))
      (node (ref "R16") (pin "2") (pinfunction "2_2") (pintype "passive"))
    )
    (net (code "64") (name "Net-(J13-Pad1)") (class "Default")
      (node (ref "J13") (pin "1") (pinfunction "1_1") (pintype "passive"))
      (node (ref "R19") (pin "2") (pinfunction "2_2") (pintype "passive"))
    )
    (net (code "65") (name "Net-(OP1-K)") (class "Default")
      (node (ref "OP1") (pin "2") (pinfunction "K_2") (pintype "passive"))
      (node (ref "R10") (pin "1") (pinfunction "1_1") (pintype "passive"))
    )
    (net (code "66") (name "Net-(Q1-D)") (class "Default")
      (node (ref "J4") (pin "1") (pinfunction "1_1") (pintype "passive"))
      (node (ref "Q1") (pin "2") (pinfunction "D_2") (pintype "passive"))
    )
    (net (code "67") (name "Net-(Q1-G)") (class "Default")
      (node (ref "Q1") (pin "1") (pinfunction "G_1") (pintype "passive"))
      (node (ref "Q2") (pin "2") (pinfunction "D_2") (pintype "passive"))
      (node (ref "R3") (pin "1") (pinfunction "1_1") (pintype "passive"))
    )
    (net (code "68") (name "Net-(Q2-G)") (class "Default")
      (node (ref "Q2") (pin "1") (pinfunction "G_1") (pintype "passive"))
      (node (ref "R7") (pin "2") (pinfunction "2_2") (pintype "passive"))
    )
    (net (code "69") (name "Net-(Q3-B)") (class "Default")
      (node (ref "Q3") (pin "1") (pinfunction "B_1") (pintype "passive"))
      (node (ref "R13") (pin "2") (pinfunction "2_2") (pintype "passive"))
    )
    (net (code "70") (name "Net-(Q3-C)") (class "Default")
      (node (ref "BUZ1") (pin "2") (pinfunction "2_2") (pintype "passive"))
      (node (ref "Q3") (pin "3") (pinfunction "C_3") (pintype "passive"))
      (node (ref "R12") (pin "1") (pinfunction "1_1") (pintype "passive"))
    )
    (net (code "71") (name "Net-(Q4-B)") (class "Default")
      (node (ref "Q4") (pin "1") (pinfunction "B_1") (pintype "passive"))
      (node (ref "R23") (pin "2") (pinfunction "2_2") (pintype "passive"))
      (node (ref "U3") (pin "3") (pinfunction "-V_3") (pintype "passive"))
    )
    (net (code "72") (name "Net-(Q4-C)") (class "Default")
      (node (ref "J2") (pin "1") (pinfunction "1_1") (pintype "passive"))
      (node (ref "Q4") (pin "3") (pinfunction "C_3") (pintype "passive"))
      (node (ref "R4") (pin "1") (pinfunction "1_1") (pintype "passive"))
    )
    (net (code "73") (name "Net-(Q4-E)") (class "Default")
      (node (ref "Q4") (pin "2") (pinfunction "E_2") (pintype "passive"))
      (node (ref "R22") (pin "2") (pinfunction "TAP_2") (pintype "passive"))
      (node (ref "U3") (pin "1") (pinfunction "ADJ_1") (pintype "input"))
    )
    (net (code "74") (name "Net-(R22-TOP)") (class "Default")
      (node (ref "R22") (pin "1") (pinfunction "TOP_1") (pintype "passive"))
      (node (ref "R5") (pin "1") (pinfunction "1_1") (pintype "passive"))
      (node (ref "U3") (pin "2") (pinfunction "+V_2") (pintype "passive"))
    )
    (net (code "75") (name "Net-(R24-BOT)") (class "Default")
      (node (ref "R2") (pin "1") (pinfunction "1_1") (pintype "passive"))
      (node (ref "R24") (pin "1") (pinfunction "BOT_1") (pintype "passive"))
      (node (ref "U1") (pin "6") (pinfunction "IN-_6") (pintype "input"))
    )
    (net (code "76") (name "Net-(R24-TAP)") (class "Default")
      (node (ref "R24") (pin "2") (pinfunction "TAP_2") (pintype "passive"))
      (node (ref "R6") (pin "2") (pinfunction "2_2") (pintype "passive"))
    )
    (net (code "77") (name "Net-(S1-COMMON)") (class "Default")
      (node (ref "J1") (pin "1") (pinfunction "1_1") (pintype "power_in"))
      (node (ref "S1") (pin "1") (pinfunction "COMMON_1") (pintype "passive"))
    )
    (net (code "78") (name "Net-(U1A-IN+)") (class "Default")
      (node (ref "J14") (pin "1") (pinfunction "1_1") (pintype "passive"))
      (node (ref "R21") (pin "1") (pinfunction "1_1") (pintype "passive"))
      (node (ref "U1") (pin "3") (pinfunction "IN+_3") (pintype "input"))
    )
    (net (code "79") (name "Net-(U1B-IN+)") (class "Default")
      (node (ref "C13") (pin "1") (pinfunction "1_1") (pintype "passive"))
      (node (ref "R8") (pin "2") (pinfunction "2_2") (pintype "passive"))
      (node (ref "U1") (pin "5") (pinfunction "IN+_5") (pintype "input"))
    )
    (net (code "80") (name "Net-(U2A-IN+)") (class "Default")
      (node (ref "C8") (pin "2") (pinfunction "2_2") (pintype "passive"))
      (node (ref "R15") (pin "2") (pinfunction "2_2") (pintype "passive"))
      (node (ref "U2") (pin "3") (pinfunction "IN+_3") (pintype "input"))
    )
    (net (code "81") (name "Net-(U2A-IN-)") (class "Default")
      (node (ref "C9") (pin "1") (pinfunction "1_1") (pintype "passive"))
      (node (ref "R17") (pin "1") (pinfunction "1_1") (pintype "passive"))
      (node (ref "R18") (pin "1") (pinfunction "1_1") (pintype "passive"))
      (node (ref "U2") (pin "2") (pinfunction "IN-_2") (pintype "input"))
    )
    (net (code "82") (name "Net-(U2B-IN+)") (class "Default")
      (node (ref "C11") (pin "2") (pinfunction "2_2") (pintype "passive"))
      (node (ref "R16") (pin "1") (pinfunction "1_1") (pintype "passive"))
      (node (ref "R20") (pin "2") (pinfunction "2_2") (pintype "passive"))
      (node (ref "U2") (pin "5") (pinfunction "IN+_5") (pintype "input"))
    )
    (net (code "83") (name "Net-(U2B-IN-)") (class "Default")
      (node (ref "C10") (pin "2") (pinfunction "2_2") (pintype "passive"))
      (node (ref "C7") (pin "2") (pinfunction "2_2") (pintype "passive"))
      (node (ref "R14") (pin "2") (pinfunction "2_2") (pintype "passive"))
      (node (ref "R19") (pin "1") (pinfunction "1_1") (pintype "passive"))
      (node (ref "U2") (pin "6") (pinfunction "IN-_6") (pintype "input"))
    )
    (net (code "84") (name "Net-(U2B-OUT)") (class "Default")
      (node (ref "C7") (pin "1") (pinfunction "1_1") (pintype "passive"))
      (node (ref "R14") (pin "1") (pinfunction "1_1") (pintype "passive"))
      (node (ref "R17") (pin "2") (pinfunction "2_2") (pintype "passive"))
      (node (ref "U2") (pin "7") (pinfunction "OUT_7") (pintype "output"))
    )
    (net (code "85") (name "unconnected-(MD1-PB0{slash}PCINT0-Pad24)") (class "Default")
      (node (ref "MD1") (pin "24") (pinfunction "PB0/PCINT0_24") (pintype "passive"))
    )
    (net (code "86") (name "unconnected-(MD1-PD0{slash}D21{slash}SCL{slash}INT0-Pad18)") (class "Default")
      (node (ref "MD1") (pin "18") (pinfunction "PD0/D21/SCL/INT0_18") (pintype "passive"))
    )
    (net (code "87") (name "unconnected-(MD1-PD1{slash}D20{slash}SDA{slash}INT1-Pad17)") (class "Default")
      (node (ref "MD1") (pin "17") (pinfunction "PD1/D20/SDA/INT1_17") (pintype "passive"))
    )
    (net (code "88") (name "unconnected-(MD1-PD2{slash}D19{slash}RXD1{slash}INT2-Pad16)") (class "Default")
      (node (ref "MD1") (pin "16") (pinfunction "PD2/D19/RXD1/INT2_16") (pintype "passive"))
    )
    (net (code "89") (name "unconnected-(MD1-PD3{slash}D18{slash}TXD1{slash}INT3-Pad15)") (class "Default")
      (node (ref "MD1") (pin "15") (pinfunction "PD3/D18/TXD1/INT3_15") (pintype "passive"))
    )
    (net (code "90") (name "unconnected-(MD1-PE0{slash}D0{slash}RXD0-Pad4)") (class "Default")
      (node (ref "MD1") (pin "4") (pinfunction "PE0/D0/RXD0_4") (pintype "passive"))
    )
    (net (code "91") (name "unconnected-(MD1-PE1{slash}D1{slash}TXD0-Pad5)") (class "Default")
      (node (ref "MD1") (pin "5") (pinfunction "PE1/D1/TXD0_5") (pintype "passive"))
    )
    (net (code "92") (name "unconnected-(MD1-PE6{slash}INT6-Pad9)") (class "Default")
      (node (ref "MD1") (pin "9") (pinfunction "PE6/INT6_9") (pintype "passive"))
    )
    (net (code "93") (name "unconnected-(MD1-PE6{slash}INT7-Pad10)") (class "Default")
      (node (ref "MD1") (pin "10") (pinfunction "PE6/INT7_10") (pintype "passive"))
    )
    (net (code "94") (name "unconnected-(MD1-PF0{slash}D54{slash}A0{slash}ADC0-Pad97)") (class "Default")
      (node (ref "MD1") (pin "97") (pinfunction "PF0/D54/A0/ADC0_97") (pintype "passive"))
    )
    (net (code "95") (name "unconnected-(MD1-PF1{slash}D55{slash}A1{slash}ADC1-Pad96)") (class "Default")
      (node (ref "MD1") (pin "96") (pinfunction "PF1/D55/A1/ADC1_96") (pintype "passive"))
    )
    (net (code "96") (name "unconnected-(MD1-PF7{slash}ADC7{slash}A7{slash}D61{slash}PCINT15-Pad52)") (class "Default")
      (node (ref "MD1") (pin "52") (pinfunction "PF7/ADC7/A7/D61/PCINT15_52") (pintype "passive"))
    )
    (net (code "97") (name "unconnected-(MD1-PH0{slash}D17{slash}RXD2-Pad14)") (class "Default")
      (node (ref "MD1") (pin "14") (pinfunction "PH0/D17/RXD2_14") (pintype "passive"))
    )
    (net (code "98") (name "unconnected-(MD1-PH2{slash}D58{slash}XCK2{slash}TX3-Pad19)") (class "Default")
      (node (ref "MD1") (pin "19") (pinfunction "PH2/D58/XCK2/TX3_19") (pintype "passive"))
    )
    (net (code "99") (name "unconnected-(MD1-PH7{slash}D60{slash}T4-Pad37)") (class "Default")
      (node (ref "MD1") (pin "37") (pinfunction "PH7/D60/T4_37") (pintype "passive"))
    )
    (net (code "100") (name "unconnected-(MD1-PJ0{slash}D15{slash}RXD3{slash}PCINT9-Pad12)") (class "Default")
      (node (ref "MD1") (pin "12") (pinfunction "PJ0/D15/RXD3/PCINT9_12") (pintype "passive"))
    )
    (net (code "101") (name "unconnected-(MD1-PJ1{slash}D14{slash}TXD3{slash}PCINT10-Pad11)") (class "Default")
      (node (ref "MD1") (pin "11") (pinfunction "PJ1/D14/TXD3/PCINT10_11") (pintype "passive"))
    )
    (net (code "102") (name "unconnected-(MD1-PK0{slash}ADC8{slash}A8PCINT16-Pad51)") (class "Default")
      (node (ref "MD1") (pin "51") (pinfunction "PK0/ADC8/A8PCINT16_51") (pintype "passive"))
    )
    (net (code "103") (name "unconnected-(MD1-PK1{slash}ADC9{slash}A9{slash}PCINT17-Pad54)") (class "Default")
      (node (ref "MD1") (pin "54") (pinfunction "PK1/ADC9/A9/PCINT17_54") (pintype "passive"))
    )
    (net (code "104") (name "unconnected-(MD1-PK2{slash}ADC10{slash}A10{slash}PCINT18-Pad53)") (class "Default")
      (node (ref "MD1") (pin "53") (pinfunction "PK2/ADC10/A10/PCINT18_53") (pintype "passive"))
    )
    (net (code "105") (name "unconnected-(MD1-PK3{slash}ADC11{slash}A11{slash}PCINT19-Pad56)") (class "Default")
      (node (ref "MD1") (pin "56") (pinfunction "PK3/ADC11/A11/PCINT19_56") (pintype "passive"))
    )
    (net (code "106") (name "unconnected-(MD1-PK4{slash}ADC12{slash}A12{slash}PCINT20-Pad55)") (class "Default")
      (node (ref "MD1") (pin "55") (pinfunction "PK4/ADC12/A12/PCINT20_55") (pintype "passive"))
    )
    (net (code "107") (name "unconnected-(MD1-PK5{slash}ADC13{slash}A13{slash}PCINT23-Pad58)") (class "Default")
      (node (ref "MD1") (pin "58") (pinfunction "PK5/ADC13/A13/PCINT23_58") (pintype "passive"))
    )
    (net (code "108") (name "unconnected-(MD1-PK6{slash}ADC14{slash}A14{slash}PCINT22-Pad57)") (class "Default")
      (node (ref "MD1") (pin "57") (pinfunction "PK6/ADC14/A14/PCINT22_57") (pintype "passive"))
    )
    (net (code "109") (name "unconnected-(MD1-Pad32)") (class "Default")
      (node (ref "MD1") (pin "32") (pinfunction "32_32") (pintype "passive"))
    )
    (net (code "110") (name "unconnected-(MD1-Pad33)") (class "Default")
      (node (ref "MD1") (pin "33") (pinfunction "33_33") (pintype "passive"))
    )
    (net (code "111") (name "unconnected-(MD1-Pad34)") (class "Default")
      (node (ref "MD1") (pin "34") (pinfunction "34_34") (pintype "passive"))
    )
    (net (code "112") (name "unconnected-(MD1-Pad35)") (class "Default")
      (node (ref "MD1") (pin "35") (pinfunction "35_35") (pintype "passive"))
    )
    (net (code "113") (name "unconnected-(MD1-Pad36)") (class "Default")
      (node (ref "MD1") (pin "36") (pinfunction "36_36") (pintype "passive"))
    )
    (net (code "114") (name "unconnected-(MD1-Pad38)") (class "Default")
      (node (ref "MD1") (pin "38") (pinfunction "38_38") (pintype "passive"))
    )
    (net (code "115") (name "unconnected-(MD1-Pad49)") (class "Default")
      (node (ref "MD1") (pin "49") (pinfunction "49_49") (pintype "passive"))
    )
    (net (code "116") (name "unconnected-(MD1-Pad50)") (class "Default")
      (node (ref "MD1") (pin "50") (pinfunction "50_50") (pintype "passive"))
    )
    (net (code "117") (name "unconnected-(MD1-Pad63)") (class "Default")
      (node (ref "MD1") (pin "63") (pinfunction "63_63") (pintype "passive"))
    )
    (net (code "118") (name "unconnected-(MD1-Pad64)") (class "Default")
      (node (ref "MD1") (pin "64") (pinfunction "64_64") (pintype "passive"))
    )
    (net (code "119") (name "unconnected-(MD1-Pad65)") (class "Default")
      (node (ref "MD1") (pin "65") (pinfunction "65_65") (pintype "passive"))
    )
    (net (code "120") (name "unconnected-(MD1-Pad66)") (class "Default")
      (node (ref "MD1") (pin "66") (pinfunction "66_66") (pintype "passive"))
    )
    (net (code "121") (name "unconnected-(MD1-Pad67)") (class "Default")
      (node (ref "MD1") (pin "67") (pinfunction "67_67") (pintype "passive"))
    )
    (net (code "122") (name "unconnected-(MD1-Pad68)") (class "Default")
      (node (ref "MD1") (pin "68") (pinfunction "68_68") (pintype "passive"))
    )
    (net (code "123") (name "unconnected-(MD1-Pad69)") (class "Default")
      (node (ref "MD1") (pin "69") (pinfunction "69_69") (pintype "passive"))
    )
    (net (code "124") (name "unconnected-(MD1-Pad70)") (class "Default")
      (node (ref "MD1") (pin "70") (pinfunction "70_70") (pintype "passive"))
    )
    (net (code "125") (name "unconnected-(MD1-Pad71)") (class "Default")
      (node (ref "MD1") (pin "71") (pinfunction "71_71") (pintype "passive"))
    )
    (net (code "126") (name "unconnected-(MD1-Pad72)") (class "Default")
      (node (ref "MD1") (pin "72") (pinfunction "72_72") (pintype "passive"))
    )
    (net (code "127") (name "unconnected-(MD1-Pad73)") (class "Default")
      (node (ref "MD1") (pin "73") (pinfunction "73_73") (pintype "passive"))
    )
    (net (code "128") (name "unconnected-(MD1-Pad74)") (class "Default")
      (node (ref "MD1") (pin "74") (pinfunction "74_74") (pintype "passive"))
    )
    (net (code "129") (name "unconnected-(MD1-Pad83)") (class "Default")
      (node (ref "MD1") (pin "83") (pinfunction "83_83") (pintype "passive"))
    )
    (net (code "130") (name "unconnected-(MD1-Pad84)") (class "Default")
      (node (ref "MD1") (pin "84") (pinfunction "84_84") (pintype "passive"))
    )
    (net (code "131") (name "unconnected-(MD1-Pad85)") (class "Default")
      (node (ref "MD1") (pin "85") (pinfunction "85_85") (pintype "passive"))
    )
    (net (code "132") (name "unconnected-(MD1-Pad86)") (class "Default")
      (node (ref "MD1") (pin "86") (pinfunction "86_86") (pintype "passive"))
    )
    (net (code "133") (name "unconnected-(MD1-Pad87)") (class "Default")
      (node (ref "MD1") (pin "87") (pinfunction "87_87") (pintype "passive"))
    )
    (net (code "134") (name "unconnected-(MD1-Pad88)") (class "Default")
      (node (ref "MD1") (pin "88") (pinfunction "88_88") (pintype "passive"))
    )
    (net (code "135") (name "unconnected-(MD1-Pad89)") (class "Default")
      (node (ref "MD1") (pin "89") (pinfunction "89_89") (pintype "passive"))
    )
    (net (code "136") (name "unconnected-(MD1-Pad90)") (class "Default")
      (node (ref "MD1") (pin "90") (pinfunction "90_90") (pintype "passive"))
    )
    (net (code "137") (name "unconnected-(MD1-Pad91)") (class "Default")
      (node (ref "MD1") (pin "91") (pinfunction "91_91") (pintype "passive"))
    )
    (net (code "138") (name "unconnected-(MD1-Pad92)") (class "Default")
      (node (ref "MD1") (pin "92") (pinfunction "92_92") (pintype "passive"))
    )
    (net (code "139") (name "unconnected-(MD1-Pad93)") (class "Default")
      (node (ref "MD1") (pin "93") (pinfunction "93_93") (pintype "passive"))
    )
    (net (code "140") (name "unconnected-(MD1-Pad94)") (class "Default")
      (node (ref "MD1") (pin "94") (pinfunction "94_94") (pintype "passive"))
    )
    (net (code "141") (name "unconnected-(MD1-Pad95)") (class "Default")
      (node (ref "MD1") (pin "95") (pinfunction "95_95") (pintype "passive"))
    )
    (net (code "142") (name "unconnected-(MD1-Pad98)") (class "Default")
      (node (ref "MD1") (pin "98") (pinfunction "98_98") (pintype "passive"))
    )
    (net (code "143") (name "unconnected-(P2-Pad21)") (class "Default")
      (node (ref "P2") (pin "21") (pinfunction "21_21") (pintype "passive"))
    )
    (net (code "144") (name "unconnected-(P2-Pad23)") (class "Default")
      (node (ref "P2") (pin "23") (pinfunction "23_23") (pintype "passive"))
    )
    (net (code "145") (name "unconnected-(P2-Pad25)") (class "Default")
      (node (ref "P2") (pin "25") (pinfunction "25_25") (pintype "passive"))
    )
    (net (code "146") (name "unconnected-(P2-Pad26)") (class "Default")
      (node (ref "P2") (pin "26") (pinfunction "26_26") (pintype "passive"))
    )
    (net (code "147") (name "unconnected-(P3-Pad21)") (class "Default")
      (node (ref "P3") (pin "21") (pinfunction "21_21") (pintype "passive"))
    )
    (net (code "148") (name "unconnected-(P3-Pad23)") (class "Default")
      (node (ref "P3") (pin "23") (pinfunction "23_23") (pintype "passive"))
    )
    (net (code "149") (name "unconnected-(P3-Pad25)") (class "Default")
      (node (ref "P3") (pin "25") (pinfunction "25_25") (pintype "passive"))
    )
    (net (code "150") (name "unconnected-(P3-Pad26)") (class "Default")
      (node (ref "P3") (pin "26") (pinfunction "26_26") (pintype "passive"))
    )
    (net (code "151") (name "unconnected-(R22-BOT-Pad3)") (class "Default")
      (node (ref "R22") (pin "3") (pinfunction "BOT_3") (pintype "passive"))
    )
    (net (code "152") (name "unconnected-(R24-TOP-Pad3)") (class "Default")
      (node (ref "R24") (pin "3") (pinfunction "TOP_3") (pintype "passive"))
    )
    (net (code "153") (name "unconnected-(S2-A4-Pad4)") (class "Default")
      (node (ref "S2") (pin "4") (pinfunction "A4_4") (pintype "passive"))
    )
  )
)
